# InputModule.net
KiCad netlist of a schematic drawn in Altium Designer
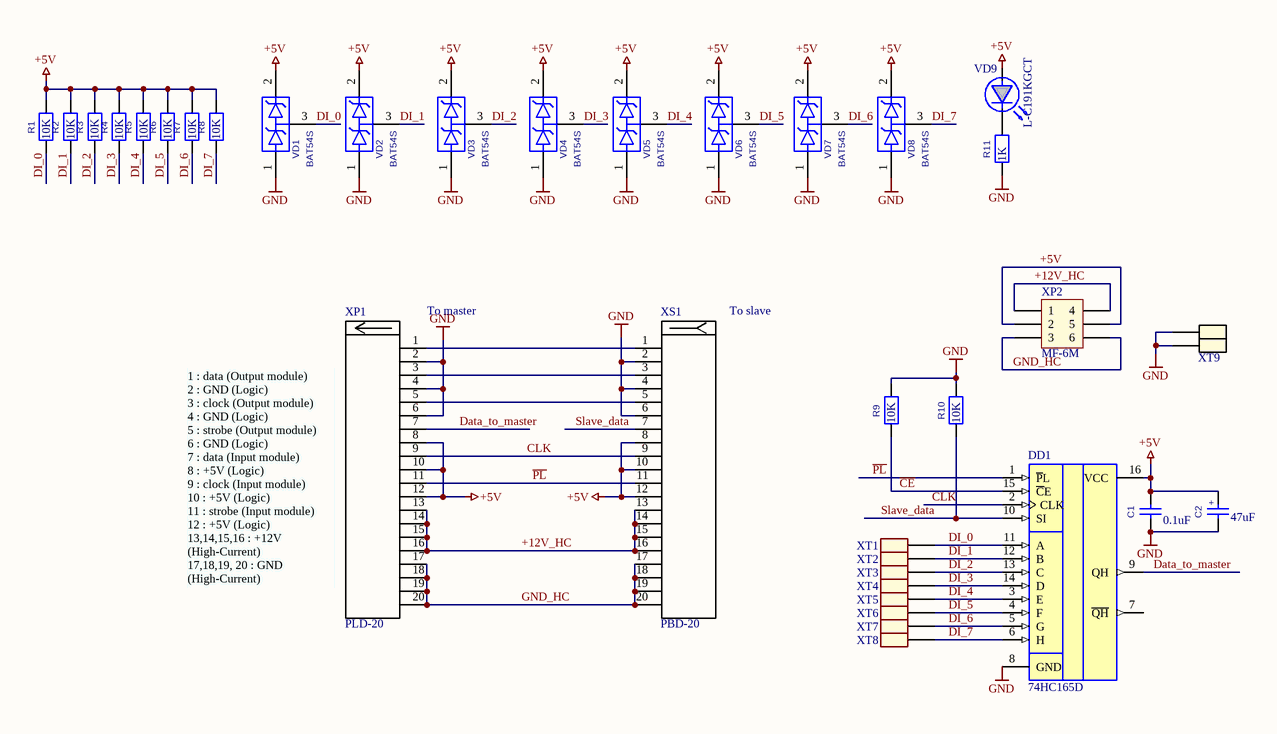
[diagram p0: InputModule.SchDoc]

(export (version "E")
  (design (tool "Eeschema 10.0.6"))
  (components
    (comp (ref "C1")
      (value "0.1uF")
      (footprint "C-1608[0603]")
      (description "C-0603")
      (libsource (lib "Altium-RC") (part "C-0603"))
    )
    (comp (ref "C2")
      (value "47uF")
      (footprint "C-CASE")
      (description "C-CCASE")
      (libsource (lib "Altium-RC") (part "C-CCASE"))
    )
    (comp (ref "DD1")
      (value "74HC165D")
      (footprint "SO-G16")
      (description "8-Bit Parallel-Load Shift Register")
      (libsource (lib "Altium-IC") (part "74HC165D"))
    )
    (comp (ref "R1")
      (value "10K")
      (footprint "R-1608[0603]")
      (description "R-0603")
      (libsource (lib "Altium-RC") (part "R-0603"))
    )
    (comp (ref "R2")
      (value "10K")
      (footprint "R-1608[0603]")
      (description "R-0603")
      (libsource (lib "Altium-RC") (part "R-0603"))
    )
    (comp (ref "R3")
      (value "10K")
      (footprint "R-1608[0603]")
      (description "R-0603")
      (libsource (lib "Altium-RC") (part "R-0603"))
    )
    (comp (ref "R4")
      (value "10K")
      (footprint "R-1608[0603]")
      (description "R-0603")
      (libsource (lib "Altium-RC") (part "R-0603"))
    )
    (comp (ref "R5")
      (value "10K")
      (footprint "R-1608[0603]")
      (description "R-0603")
      (libsource (lib "Altium-RC") (part "R-0603"))
    )
    (comp (ref "R6")
      (value "10K")
      (footprint "R-1608[0603]")
      (description "R-0603")
      (libsource (lib "Altium-RC") (part "R-0603"))
    )
    (comp (ref "R7")
      (value "10K")
      (footprint "R-1608[0603]")
      (description "R-0603")
      (libsource (lib "Altium-RC") (part "R-0603"))
    )
    (comp (ref "R8")
      (value "10K")
      (footprint "R-1608[0603]")
      (description "R-0603")
      (libsource (lib "Altium-RC") (part "R-0603"))
    )
    (comp (ref "R9")
      (value "10K")
      (footprint "R-1608[0603]")
      (description "R-0603")
      (libsource (lib "Altium-RC") (part "R-0603"))
    )
    (comp (ref "R10")
      (value "10K")
      (footprint "R-1608[0603]")
      (description "R-0603")
      (libsource (lib "Altium-RC") (part "R-0603"))
    )
    (comp (ref "R11")
      (value "1K")
      (footprint "R-1608[0603]")
      (description "R-0603")
      (libsource (lib "Altium-RC") (part "R-0603"))
    )
    (comp (ref "VD1")
      (value "BAT54S")
      (footprint "SOT-23")
      (description "Schottky barrier (double) diodes")
      (libsource (lib "Altium-RECT") (part "BAT54S"))
    )
    (comp (ref "VD2")
      (value "BAT54S")
      (footprint "SOT-23")
      (description "Schottky barrier (double) diodes")
      (libsource (lib "Altium-RECT") (part "BAT54S"))
    )
    (comp (ref "VD3")
      (value "BAT54S")
      (footprint "SOT-23")
      (description "Schottky barrier (double) diodes")
      (libsource (lib "Altium-RECT") (part "BAT54S"))
    )
    (comp (ref "VD4")
      (value "BAT54S")
      (footprint "SOT-23")
      (description "Schottky barrier (double) diodes")
      (libsource (lib "Altium-RECT") (part "BAT54S"))
    )
    (comp (ref "VD5")
      (value "BAT54S")
      (footprint "SOT-23")
      (description "Schottky barrier (double) diodes")
      (libsource (lib "Altium-RECT") (part "BAT54S"))
    )
    (comp (ref "VD6")
      (value "BAT54S")
      (footprint "SOT-23")
      (description "Schottky barrier (double) diodes")
      (libsource (lib "Altium-RECT") (part "BAT54S"))
    )
    (comp (ref "VD7")
      (value "BAT54S")
      (footprint "SOT-23")
      (description "Schottky barrier (double) diodes")
      (libsource (lib "Altium-RECT") (part "BAT54S"))
    )
    (comp (ref "VD8")
      (value "BAT54S")
      (footprint "SOT-23")
      (description "Schottky barrier (double) diodes")
      (libsource (lib "Altium-RECT") (part "BAT54S"))
    )
    (comp (ref "VD9")
      (value "L-C191KGCT")
      (footprint "LED-0603")
      (description "0603 Green Led")
      (libsource (lib "Altium-OPTO") (part "L-C191KGCT"))
    )
    (comp (ref "XP1")
      (value "PLD-20")
      (footprint "PLD-20 ROT")
      (description "20 pin, 2 row, MALE connector")
      (libsource (lib "Altium-CONN") (part "PLD-20"))
    )
    (comp (ref "XP2")
      (value "MF-6M")
      (footprint "MF-6M")
      (description "Molex Male connector")
      (libsource (lib "Altium-CONN") (part "MF-6M"))
    )
    (comp (ref "XS1")
      (value "PBD-20")
      (footprint "PBD-20 Rot")
      (description "2.54mm, 20 pin FEMALE connector")
      (libsource (lib "Altium-CONN") (part "PBD-20"))
    )
    (comp (ref "XT1")
      (value "DG141V-01P")
      (footprint "DG141V-01P (XY123R)")
      (description "Клеммник нажимной 2.54мм")
      (libsource (lib "Altium-CONN") (part "DG141V-01P"))
    )
    (comp (ref "XT2")
      (value "DG141V-01P")
      (footprint "DG141V-01P (XY123R)")
      (description "Клеммник нажимной 2.54мм")
      (libsource (lib "Altium-CONN") (part "DG141V-01P"))
    )
    (comp (ref "XT3")
      (value "DG141V-01P")
      (footprint "DG141V-01P (XY123R)")
      (description "Клеммник нажимной 2.54мм")
      (libsource (lib "Altium-CONN") (part "DG141V-01P"))
    )
    (comp (ref "XT4")
      (value "DG141V-01P")
      (footprint "DG141V-01P (XY123R)")
      (description "Клеммник нажимной 2.54мм")
      (libsource (lib "Altium-CONN") (part "DG141V-01P"))
    )
    (comp (ref "XT5")
      (value "DG141V-01P")
      (footprint "DG141V-01P (XY123R)")
      (description "Клеммник нажимной 2.54мм")
      (libsource (lib "Altium-CONN") (part "DG141V-01P"))
    )
    (comp (ref "XT6")
      (value "DG141V-01P")
      (footprint "DG141V-01P (XY123R)")
      (description "Клеммник нажимной 2.54мм")
      (libsource (lib "Altium-CONN") (part "DG141V-01P"))
    )
    (comp (ref "XT7")
      (value "DG141V-01P")
      (footprint "DG141V-01P (XY123R)")
      (description "Клеммник нажимной 2.54мм")
      (libsource (lib "Altium-CONN") (part "DG141V-01P"))
    )
    (comp (ref "XT8")
      (value "DG141V-01P")
      (footprint "DG141V-01P (XY123R)")
      (description "Клеммник нажимной 2.54мм")
      (libsource (lib "Altium-CONN") (part "DG141V-01P"))
    )
    (comp (ref "XT9")
      (value "1-1776244-0 (TYCO)")
      (footprint "1-1776244-0")
      (description "Винтовой клеммник 5.0мм")
      (libsource (lib "Altium-CONN") (part "1-1776244-0 (TYCO)"))
    )
  )
  (nets
    (net (code "1") (name "+5V") (class "Default")
      (node (ref "C1") (pin "1") (pintype "passive"))
      (node (ref "C2") (pin "1") (pinfunction "+_1") (pintype "passive"))
      (node (ref "DD1") (pin "16") (pinfunction "VCC_16") (pintype "power_in"))
      (node (ref "R1") (pin "2") (pinfunction "2_2") (pintype "passive"))
      (node (ref "R2") (pin "2") (pinfunction "2_2") (pintype "passive"))
      (node (ref "R3") (pin "2") (pinfunction "2_2") (pintype "passive"))
      (node (ref "R4") (pin "2") (pinfunction "2_2") (pintype "passive"))
      (node (ref "R5") (pin "2") (pinfunction "2_2") (pintype "passive"))
      (node (ref "R6") (pin "2") (pinfunction "2_2") (pintype "passive"))
      (node (ref "R7") (pin "2") (pinfunction "2_2") (pintype "passive"))
      (node (ref "R8") (pin "2") (pinfunction "2_2") (pintype "passive"))
      (node (ref "VD1") (pin "2") (pinfunction "c_2") (pintype "passive"))
      (node (ref "VD2") (pin "2") (pinfunction "c_2") (pintype "passive"))
      (node (ref "VD3") (pin "2") (pinfunction "c_2") (pintype "passive"))
      (node (ref "VD4") (pin "2") (pinfunction "c_2") (pintype "passive"))
      (node (ref "VD5") (pin "2") (pinfunction "c_2") (pintype "passive"))
      (node (ref "VD6") (pin "2") (pinfunction "c_2") (pintype "passive"))
      (node (ref "VD7") (pin "2") (pinfunction "c_2") (pintype "passive"))
      (node (ref "VD8") (pin "2") (pinfunction "c_2") (pintype "passive"))
      (node (ref "VD9") (pin "2") (pinfunction "A_2") (pintype "passive"))
      (node (ref "XP1") (pin "10") (pintype "passive"))
      (node (ref "XP1") (pin "12") (pintype "passive"))
      (node (ref "XP1") (pin "8") (pintype "passive"))
      (node (ref "XP2") (pin "2") (pinfunction "2_2") (pintype "passive"))
      (node (ref "XP2") (pin "5") (pinfunction "5_5") (pintype "passive"))
      (node (ref "XS1") (pin "10") (pintype "passive"))
      (node (ref "XS1") (pin "12") (pintype "passive"))
      (node (ref "XS1") (pin "8") (pintype "passive"))
    )
    (net (code "2") (name "/+12V_HC") (class "Default")
      (node (ref "XP1") (pin "13") (pintype "passive"))
      (node (ref "XP1") (pin "14") (pintype "passive"))
      (node (ref "XP1") (pin "15") (pintype "passive"))
      (node (ref "XP1") (pin "16") (pintype "passive"))
      (node (ref "XP2") (pin "1") (pinfunction "1_1") (pintype "passive"))
      (node (ref "XP2") (pin "4") (pinfunction "4_4") (pintype "passive"))
      (node (ref "XS1") (pin "13") (pintype "passive"))
      (node (ref "XS1") (pin "14") (pintype "passive"))
      (node (ref "XS1") (pin "15") (pintype "passive"))
      (node (ref "XS1") (pin "16") (pintype "passive"))
    )
    (net (code "3") (name "/CLK") (class "Default")
      (node (ref "DD1") (pin "2") (pinfunction "CLK_2") (pintype "input"))
      (node (ref "XP1") (pin "9") (pintype "passive"))
      (node (ref "XS1") (pin "9") (pintype "passive"))
    )
    (net (code "4") (name "/DI_0") (class "Default")
      (node (ref "DD1") (pin "11") (pinfunction "A_11") (pintype "input"))
      (node (ref "R1") (pin "1") (pinfunction "1_1") (pintype "passive"))
      (node (ref "VD1") (pin "3") (pinfunction "ka_3") (pintype "passive"))
      (node (ref "XT1") (pin "1") (pintype "passive"))
    )
    (net (code "5") (name "/DI_1") (class "Default")
      (node (ref "DD1") (pin "12") (pinfunction "B_12") (pintype "input"))
      (node (ref "R2") (pin "1") (pinfunction "1_1") (pintype "passive"))
      (node (ref "VD2") (pin "3") (pinfunction "ka_3") (pintype "passive"))
      (node (ref "XT2") (pin "1") (pintype "passive"))
    )
    (net (code "6") (name "/DI_2") (class "Default")
      (node (ref "DD1") (pin "13") (pinfunction "C_13") (pintype "input"))
      (node (ref "R3") (pin "1") (pinfunction "1_1") (pintype "passive"))
      (node (ref "VD3") (pin "3") (pinfunction "ka_3") (pintype "passive"))
      (node (ref "XT3") (pin "1") (pintype "passive"))
    )
    (net (code "7") (name "/DI_3") (class "Default")
      (node (ref "DD1") (pin "14") (pinfunction "D_14") (pintype "input"))
      (node (ref "R4") (pin "1") (pinfunction "1_1") (pintype "passive"))
      (node (ref "VD4") (pin "3") (pinfunction "ka_3") (pintype "passive"))
      (node (ref "XT4") (pin "1") (pintype "passive"))
    )
    (net (code "8") (name "/DI_4") (class "Default")
      (node (ref "DD1") (pin "3") (pinfunction "E_3") (pintype "input"))
      (node (ref "R5") (pin "1") (pinfunction "1_1") (pintype "passive"))
      (node (ref "VD5") (pin "3") (pinfunction "ka_3") (pintype "passive"))
      (node (ref "XT5") (pin "1") (pintype "passive"))
    )
    (net (code "9") (name "/DI_5") (class "Default")
      (node (ref "DD1") (pin "4") (pinfunction "F_4") (pintype "input"))
      (node (ref "R6") (pin "1") (pinfunction "1_1") (pintype "passive"))
      (node (ref "VD6") (pin "3") (pinfunction "ka_3") (pintype "passive"))
      (node (ref "XT6") (pin "1") (pintype "passive"))
    )
    (net (code "10") (name "/DI_6") (class "Default")
      (node (ref "DD1") (pin "5") (pinfunction "G_5") (pintype "input"))
      (node (ref "R7") (pin "1") (pinfunction "1_1") (pintype "passive"))
      (node (ref "VD7") (pin "3") (pinfunction "ka_3") (pintype "passive"))
      (node (ref "XT7") (pin "1") (pintype "passive"))
    )
    (net (code "11") (name "/DI_7") (class "Default")
      (node (ref "DD1") (pin "6") (pinfunction "H_6") (pintype "input"))
      (node (ref "R8") (pin "1") (pinfunction "1_1") (pintype "passive"))
      (node (ref "VD8") (pin "3") (pinfunction "ka_3") (pintype "passive"))
      (node (ref "XT8") (pin "1") (pintype "passive"))
    )
    (net (code "12") (name "/Data_to_master") (class "Default")
      (node (ref "DD1") (pin "9") (pinfunction "QH_9") (pintype "output"))
      (node (ref "XP1") (pin "7") (pintype "passive"))
    )
    (net (code "13") (name "/GND_HC") (class "Default")
      (node (ref "XP1") (pin "17") (pintype "passive"))
      (node (ref "XP1") (pin "18") (pintype "passive"))
      (node (ref "XP1") (pin "19") (pintype "passive"))
      (node (ref "XP1") (pin "20") (pintype "passive"))
      (node (ref "XP2") (pin "3") (pinfunction "3_3") (pintype "passive"))
      (node (ref "XP2") (pin "6") (pinfunction "6_6") (pintype "passive"))
      (node (ref "XS1") (pin "17") (pintype "passive"))
      (node (ref "XS1") (pin "18") (pintype "passive"))
      (node (ref "XS1") (pin "19") (pintype "passive"))
      (node (ref "XS1") (pin "20") (pintype "passive"))
    )
    (net (code "14") (name "/Slave_data") (class "Default")
      (node (ref "DD1") (pin "10") (pinfunction "SI_10") (pintype "input"))
      (node (ref "R10") (pin "1") (pinfunction "1_1") (pintype "passive"))
      (node (ref "XS1") (pin "7") (pintype "passive"))
    )
    (net (code "15") (name "/~{CE}") (class "Default")
      (node (ref "DD1") (pin "15") (pinfunction "~{C}E_15") (pintype "input"))
      (node (ref "R9") (pin "1") (pinfunction "1_1") (pintype "passive"))
    )
    (net (code "16") (name "/~{PL}") (class "Default")
      (node (ref "DD1") (pin "1") (pinfunction "~{P}L_1") (pintype "input"))
      (node (ref "XP1") (pin "11") (pintype "passive"))
      (node (ref "XS1") (pin "11") (pintype "passive"))
    )
    (net (code "17") (name "GND") (class "Default")
      (node (ref "C1") (pin "2") (pintype "passive"))
      (node (ref "C2") (pin "2") (pinfunction "-_2") (pintype "passive"))
      (node (ref "DD1") (pin "8") (pinfunction "GND_8") (pintype "power_in"))
      (node (ref "R10") (pin "2") (pinfunction "2_2") (pintype "passive"))
      (node (ref "R11") (pin "1") (pinfunction "1_1") (pintype "passive"))
      (node (ref "R9") (pin "2") (pinfunction "2_2") (pintype "passive"))
      (node (ref "VD1") (pin "1") (pinfunction "a_1") (pintype "passive"))
      (node (ref "VD2") (pin "1") (pinfunction "a_1") (pintype "passive"))
      (node (ref "VD3") (pin "1") (pinfunction "a_1") (pintype "passive"))
      (node (ref "VD4") (pin "1") (pinfunction "a_1") (pintype "passive"))
      (node (ref "VD5") (pin "1") (pinfunction "a_1") (pintype "passive"))
      (node (ref "VD6") (pin "1") (pinfunction "a_1") (pintype "passive"))
      (node (ref "VD7") (pin "1") (pinfunction "a_1") (pintype "passive"))
      (node (ref "VD8") (pin "1") (pinfunction "a_1") (pintype "passive"))
      (node (ref "XP1") (pin "2") (pintype "passive"))
      (node (ref "XP1") (pin "4") (pintype "passive"))
      (node (ref "XP1") (pin "6") (pintype "passive"))
      (node (ref "XS1") (pin "2") (pintype "passive"))
      (node (ref "XS1") (pin "4") (pintype "passive"))
      (node (ref "XS1") (pin "6") (pintype "passive"))
      (node (ref "XT9") (pin "1") (pintype "passive"))
      (node (ref "XT9") (pin "2") (pintype "passive"))
    )
    (net (code "18") (name "Net-(VD9-K)") (class "Default")
      (node (ref "R11") (pin "2") (pinfunction "2_2") (pintype "passive"))
      (node (ref "VD9") (pin "1") (pinfunction "K_1") (pintype "passive"))
    )
    (net (code "19") (name "Net-(XP1-Pad1)") (class "Default")
      (node (ref "XP1") (pin "1") (pintype "passive"))
      (node (ref "XS1") (pin "1") (pintype "passive"))
    )
    (net (code "20") (name "Net-(XP1-Pad3)") (class "Default")
      (node (ref "XP1") (pin "3") (pintype "passive"))
      (node (ref "XS1") (pin "3") (pintype "passive"))
    )
    (net (code "21") (name "Net-(XP1-Pad5)") (class "Default")
      (node (ref "XP1") (pin "5") (pintype "passive"))
      (node (ref "XS1") (pin "5") (pintype "passive"))
    )
    (net (code "22") (name "unconnected-(DD1-~{QH}-Pad7)") (class "Default")
      (node (ref "DD1") (pin "7") (pinfunction "~{QH}_7") (pintype "output"))
    )
  )
)
